# LPCB225_-_STACK_CONNECTORS.net
KiCad netlist of a schematic drawn in Altium Designer
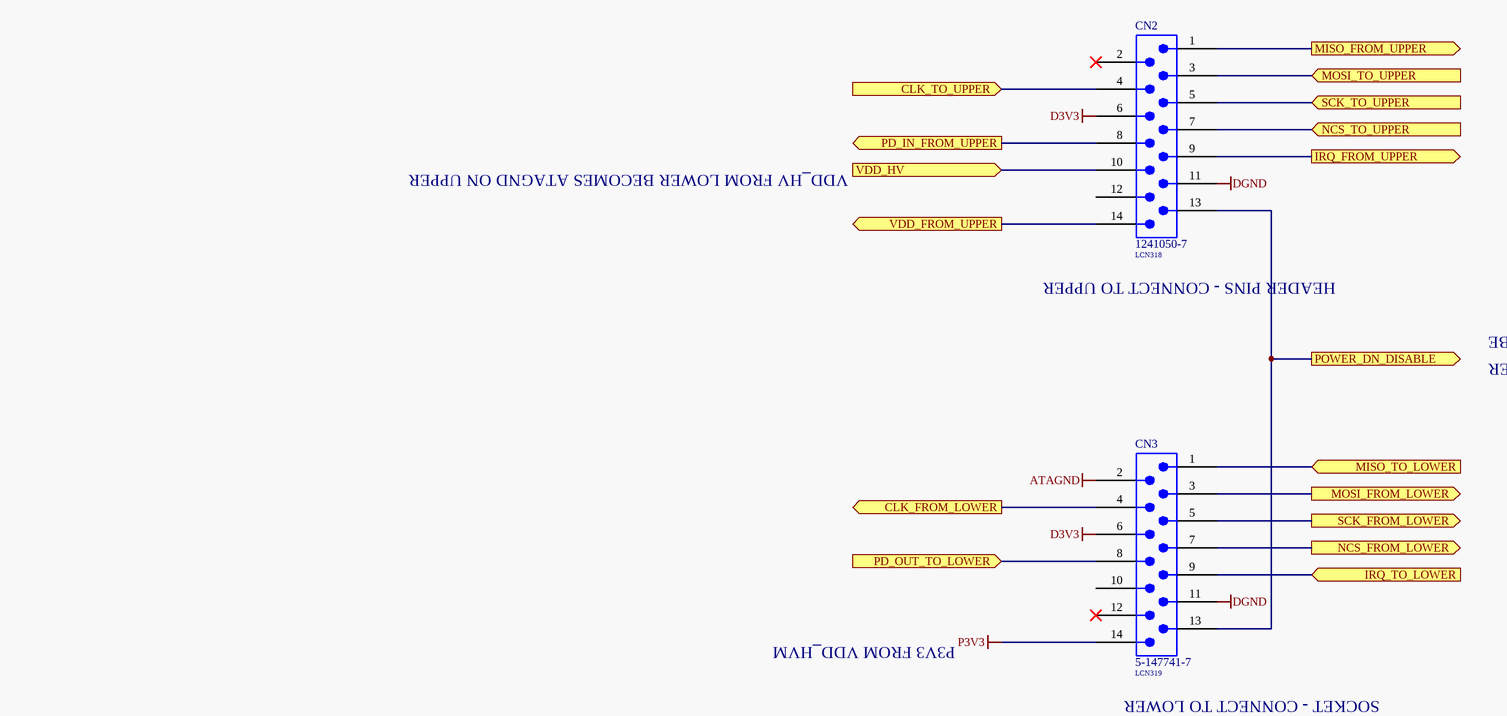
[diagram p0: LPCB225 - STACK CONNECTORS.SchDoc]

(export (version "E")
  (design (tool "Eeschema 10.0.6"))
  (components
    (comp (ref "CN2")
      (value "1241050-7")
      (footprint "1241050-7")
      (description "Connector, Header, 2.54mm, 7 Pins x 2 Rows, SMD")
      (fields (field (name "LDL_NUMBER") "LCN318"))
      (libsource (lib "LDL_Connectors") (part "1241050-7"))
    )
    (comp (ref "CN3")
      (value "5-147741-7")
      (footprint "5-147741-7")
      (description "Connector, Socket, 2.54mm, 7 pins x 2 Rows, SMD")
      (fields (field (name "LDL_NUMBER") "LCN319"))
      (libsource (lib "LDL_Connectors") (part "5-147741-7"))
    )
  )
  (nets
    (net (code "1") (name "/CLK_FROM_LOWER") (class "Default")
      (node (ref "CN3") (pin "4") (pinfunction "4_4") (pintype "passive"))
    )
    (net (code "2") (name "/CLK_TO_UPPER") (class "Default")
      (node (ref "CN2") (pin "4") (pinfunction "4_4") (pintype "passive"))
    )
    (net (code "3") (name "/IRQ_FROM_UPPER") (class "Default")
      (node (ref "CN2") (pin "9") (pinfunction "9_9") (pintype "passive"))
    )
    (net (code "4") (name "/IRQ_TO_LOWER") (class "Default")
      (node (ref "CN3") (pin "9") (pinfunction "9_9") (pintype "passive"))
    )
    (net (code "5") (name "/MISO_FROM_UPPER") (class "Default")
      (node (ref "CN2") (pin "1") (pinfunction "1_1") (pintype "passive"))
    )
    (net (code "6") (name "/MISO_TO_LOWER") (class "Default")
      (node (ref "CN3") (pin "1") (pinfunction "1_1") (pintype "passive"))
    )
    (net (code "7") (name "/MOSI_FROM_LOWER") (class "Default")
      (node (ref "CN3") (pin "3") (pinfunction "3_3") (pintype "passive"))
    )
    (net (code "8") (name "/MOSI_TO_UPPER") (class "Default")
      (node (ref "CN2") (pin "3") (pinfunction "3_3") (pintype "passive"))
    )
    (net (code "9") (name "/NCS_FROM_LOWER") (class "Default")
      (node (ref "CN3") (pin "7") (pinfunction "7_7") (pintype "passive"))
    )
    (net (code "10") (name "/NCS_TO_UPPER") (class "Default")
      (node (ref "CN2") (pin "7") (pinfunction "7_7") (pintype "passive"))
    )
    (net (code "11") (name "/PD_IN_FROM_UPPER") (class "Default")
      (node (ref "CN2") (pin "8") (pinfunction "8_8") (pintype "passive"))
    )
    (net (code "12") (name "/PD_OUT_TO_LOWER") (class "Default")
      (node (ref "CN3") (pin "8") (pinfunction "8_8") (pintype "passive"))
    )
    (net (code "13") (name "/POWER_DN_DISABLE") (class "Default")
      (node (ref "CN2") (pin "13") (pinfunction "13_13") (pintype "passive"))
      (node (ref "CN3") (pin "13") (pinfunction "13_13") (pintype "passive"))
    )
    (net (code "14") (name "/SCK_FROM_LOWER") (class "Default")
      (node (ref "CN3") (pin "5") (pinfunction "5_5") (pintype "passive"))
    )
    (net (code "15") (name "/SCK_TO_UPPER") (class "Default")
      (node (ref "CN2") (pin "5") (pinfunction "5_5") (pintype "passive"))
    )
    (net (code "16") (name "/VDD_FROM_UPPER") (class "Default")
      (node (ref "CN2") (pin "14") (pinfunction "14_14") (pintype "passive"))
    )
    (net (code "17") (name "/VDD_HV") (class "Default")
      (node (ref "CN2") (pin "10") (pinfunction "10_10") (pintype "passive"))
    )
    (net (code "18") (name "ATAGND") (class "Default")
      (node (ref "CN3") (pin "2") (pinfunction "2_2") (pintype "passive"))
    )
    (net (code "19") (name "D3V3") (class "Default")
      (node (ref "CN2") (pin "6") (pinfunction "6_6") (pintype "passive"))
      (node (ref "CN3") (pin "6") (pinfunction "6_6") (pintype "passive"))
    )
    (net (code "20") (name "DGND") (class "Default")
      (node (ref "CN2") (pin "11") (pinfunction "11_11") (pintype "passive"))
      (node (ref "CN3") (pin "11") (pinfunction "11_11") (pintype "passive"))
    )
    (net (code "21") (name "P3V3") (class "Default")
      (node (ref "CN3") (pin "14") (pinfunction "14_14") (pintype "passive"))
    )
    (net (code "22") (name "unconnected-(CN2-Pad2)") (class "Default")
      (node (ref "CN2") (pin "2") (pinfunction "2_2") (pintype "passive+no_connect"))
    )
    (net (code "23") (name "unconnected-(CN2-Pad12)") (class "Default")
      (node (ref "CN2") (pin "12") (pinfunction "12_12") (pintype "passive"))
    )
    (net (code "24") (name "unconnected-(CN3-Pad10)") (class "Default")
      (node (ref "CN3") (pin "10") (pinfunction "10_10") (pintype "passive"))
    )
    (net (code "25") (name "unconnected-(CN3-Pad12)") (class "Default")
      (node (ref "CN3") (pin "12") (pinfunction "12_12") (pintype "passive+no_connect"))
    )
  )
)
